# Trimble_Thunderbolt_Monitor_Shield_v1_0.net
KiCad netlist of a schematic drawn in EAGLE
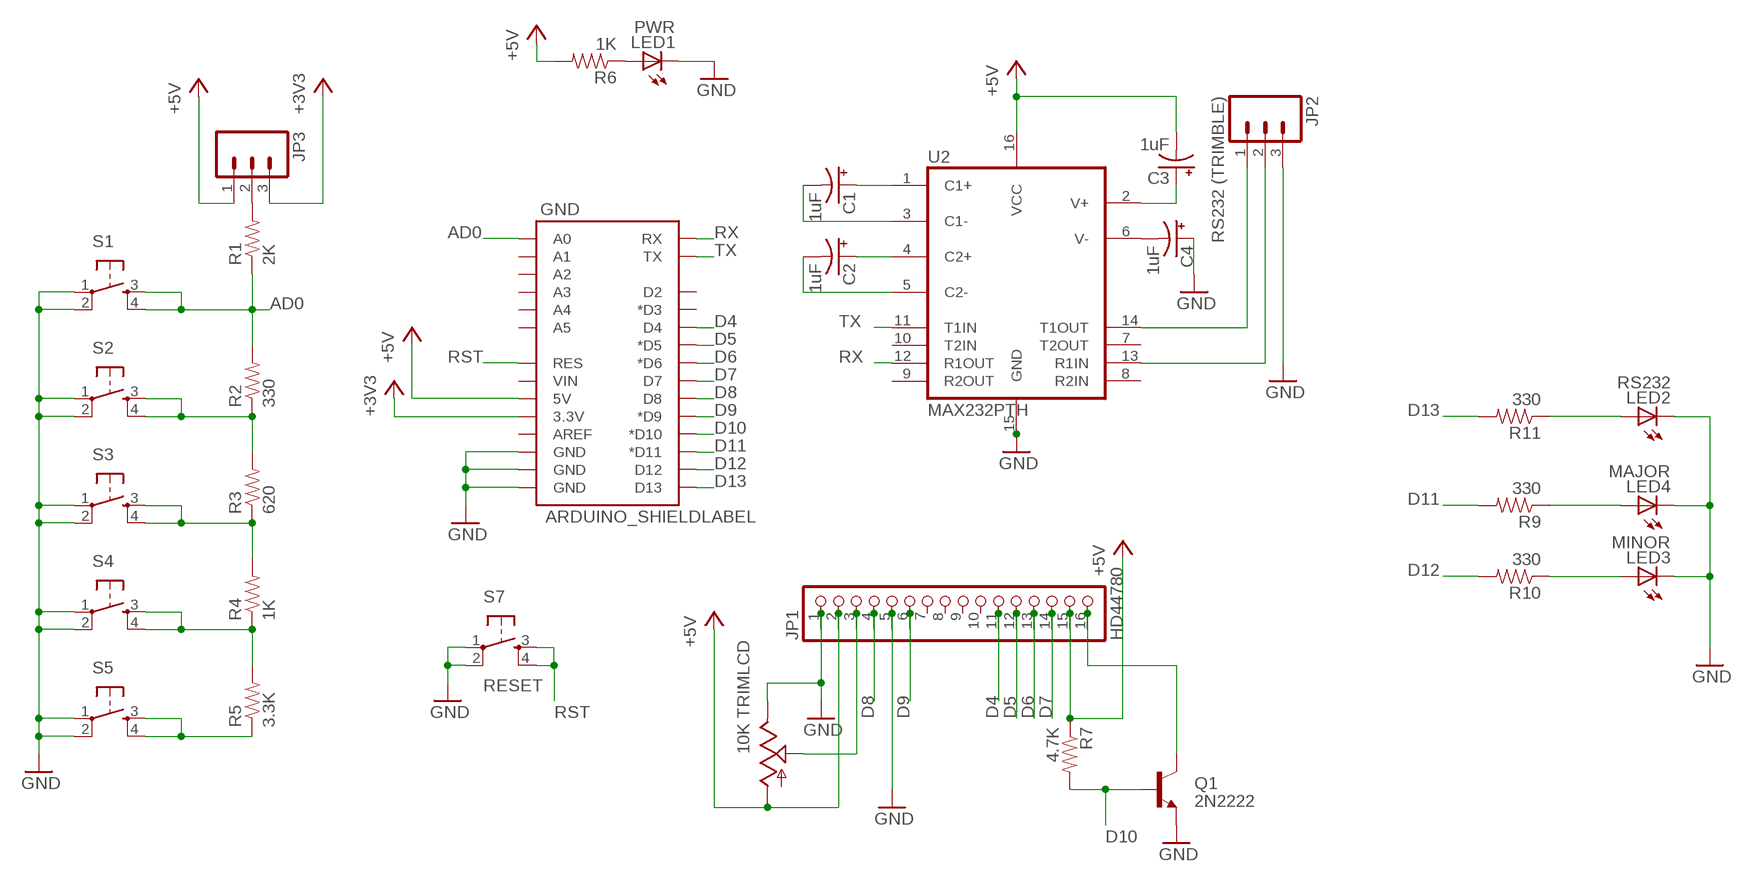
[diagram p0: schematic, sheet 1]

(export (version "E")
  (design (tool "Eeschema 10.0.6"))
  (components
    (comp (ref "C1")
      (value "1uF")
      (footprint "eagle-import:CPOL-RADIAL-10UF-25V")
      (libsource (lib "eagle-import") (part "CAP_POLPTH2"))
    )
    (comp (ref "C2")
      (value "1uF")
      (footprint "eagle-import:CPOL-RADIAL-10UF-25V")
      (libsource (lib "eagle-import") (part "CAP_POLPTH2"))
    )
    (comp (ref "C3")
      (value "1uF")
      (footprint "eagle-import:CPOL-RADIAL-10UF-25V")
      (libsource (lib "eagle-import") (part "CAP_POLPTH2"))
    )
    (comp (ref "C4")
      (value "1uF")
      (footprint "eagle-import:CPOL-RADIAL-10UF-25V")
      (libsource (lib "eagle-import") (part "CAP_POLPTH2"))
    )
    (comp (ref "GND")
      (value "ARDUINO_SHIELDLABEL")
      (footprint "eagle-import:DUEMILANOVE_SHIELD")
      (libsource (lib "eagle-import") (part "ARDUINO_SHIELDLABEL"))
    )
    (comp (ref "JP1")
      (value "HD44780")
      (footprint "eagle-import:1X16")
      (libsource (lib "eagle-import") (part "PINHD-1X16"))
    )
    (comp (ref "JP2")
      (value "RS232 (TRIMBLE)")
      (footprint "eagle-import:MOLEX-1X3")
      (libsource (lib "eagle-import") (part "M03POLAR"))
    )
    (comp (ref "JP3")
      (value "M03PTH")
      (footprint "eagle-import:1X03")
      (libsource (lib "eagle-import") (part "M03PTH"))
    )
    (comp (ref "LED1")
      (value "PWR")
      (footprint "eagle-import:LED5MM")
      (libsource (lib "eagle-import") (part "LED5MM"))
    )
    (comp (ref "LED2")
      (value "RS232")
      (footprint "eagle-import:LED5MM")
      (libsource (lib "eagle-import") (part "LED5MM"))
    )
    (comp (ref "LED3")
      (value "MINOR")
      (footprint "eagle-import:LED5MM")
      (libsource (lib "eagle-import") (part "LED5MM"))
    )
    (comp (ref "LED4")
      (value "MAJOR")
      (footprint "eagle-import:LED5MM")
      (libsource (lib "eagle-import") (part "LED5MM"))
    )
    (comp (ref "Q1")
      (value "2N2222")
      (footprint "eagle-import:TO-92-AMMO")
      (libsource (lib "eagle-import") (part "TRANSISTOR_NPNTO-92-AMMO"))
    )
    (comp (ref "R1")
      (value "2K")
      (footprint "eagle-import:AXIAL-0.3")
      (libsource (lib "eagle-import") (part "RESISTORAXIAL-0.3"))
    )
    (comp (ref "R2")
      (value "330")
      (footprint "eagle-import:AXIAL-0.3")
      (libsource (lib "eagle-import") (part "RESISTORAXIAL-0.3"))
    )
    (comp (ref "R3")
      (value "620")
      (footprint "eagle-import:AXIAL-0.3")
      (libsource (lib "eagle-import") (part "RESISTORAXIAL-0.3"))
    )
    (comp (ref "R4")
      (value "1K")
      (footprint "eagle-import:AXIAL-0.3")
      (libsource (lib "eagle-import") (part "RESISTORAXIAL-0.3"))
    )
    (comp (ref "R5")
      (value "3.3K")
      (footprint "eagle-import:AXIAL-0.3")
      (libsource (lib "eagle-import") (part "RESISTORAXIAL-0.3"))
    )
    (comp (ref "R6")
      (value "1K")
      (footprint "eagle-import:AXIAL-0.3")
      (libsource (lib "eagle-import") (part "RESISTORAXIAL-0.3"))
    )
    (comp (ref "R7")
      (value "4.7K")
      (footprint "eagle-import:AXIAL-0.3")
      (libsource (lib "eagle-import") (part "RESISTORAXIAL-0.3"))
    )
    (comp (ref "R9")
      (value "330")
      (footprint "eagle-import:AXIAL-0.3")
      (libsource (lib "eagle-import") (part "RESISTORAXIAL-0.3"))
    )
    (comp (ref "R10")
      (value "330")
      (footprint "eagle-import:AXIAL-0.3")
      (libsource (lib "eagle-import") (part "RESISTORAXIAL-0.3"))
    )
    (comp (ref "R11")
      (value "330")
      (footprint "eagle-import:AXIAL-0.3")
      (libsource (lib "eagle-import") (part "RESISTORAXIAL-0.3"))
    )
    (comp (ref "S1")
      (value "TAC_SWITCHPTH")
      (footprint "eagle-import:TACTILE-PTH")
      (libsource (lib "eagle-import") (part "TAC_SWITCHPTH"))
    )
    (comp (ref "S2")
      (value "TAC_SWITCHPTH")
      (footprint "eagle-import:TACTILE-PTH")
      (libsource (lib "eagle-import") (part "TAC_SWITCHPTH"))
    )
    (comp (ref "S3")
      (value "TAC_SWITCHPTH")
      (footprint "eagle-import:TACTILE-PTH")
      (libsource (lib "eagle-import") (part "TAC_SWITCHPTH"))
    )
    (comp (ref "S4")
      (value "TAC_SWITCHPTH")
      (footprint "eagle-import:TACTILE-PTH")
      (libsource (lib "eagle-import") (part "TAC_SWITCHPTH"))
    )
    (comp (ref "S5")
      (value "TAC_SWITCHPTH")
      (footprint "eagle-import:TACTILE-PTH")
      (libsource (lib "eagle-import") (part "TAC_SWITCHPTH"))
    )
    (comp (ref "S7")
      (value "RESET")
      (footprint "eagle-import:TACTILE-PTH")
      (libsource (lib "eagle-import") (part "TAC_SWITCHPTH"))
    )
    (comp (ref "TRIMLCD")
      (value "10K")
      (footprint "eagle-import:3362U")
      (libsource (lib "eagle-import") (part "POT100K_3362U"))
    )
    (comp (ref "U2")
      (value "MAX232PTH")
      (footprint "eagle-import:DIL16")
      (libsource (lib "eagle-import") (part "MAX232PTH"))
    )
  )
  (nets
    (net (code "1") (name "+3V3") (class "Default")
      (node (ref "GND") (pin "3.3V") (pinfunction "3.3V_3.3V") (pintype "bidirectional"))
      (node (ref "JP3") (pin "3") (pinfunction "3_3") (pintype "passive"))
    )
    (net (code "2") (name "+5V") (class "Default")
      (node (ref "C3") (pin "2") (pinfunction "-_2") (pintype "passive"))
      (node (ref "GND") (pin "5V") (pinfunction "5V_5V") (pintype "bidirectional"))
      (node (ref "JP1") (pin "15") (pinfunction "15_15") (pintype "passive"))
      (node (ref "JP1") (pin "2") (pinfunction "2_2") (pintype "passive"))
      (node (ref "JP3") (pin "1") (pinfunction "1_1") (pintype "passive"))
      (node (ref "R6") (pin "P$2") (pinfunction "2_P$2") (pintype "passive"))
      (node (ref "R7") (pin "P$1") (pinfunction "1_P$1") (pintype "passive"))
      (node (ref "TRIMLCD") (pin "P$3") (pinfunction "A_P$3") (pintype "passive"))
      (node (ref "U2") (pin "16") (pinfunction "VCC_16") (pintype "bidirectional"))
    )
    (net (code "3") (name "/AD0") (class "Default")
      (node (ref "GND") (pin "A0") (pinfunction "A0_A0") (pintype "bidirectional"))
      (node (ref "R1") (pin "P$1") (pinfunction "1_P$1") (pintype "passive"))
      (node (ref "R2") (pin "P$2") (pinfunction "2_P$2") (pintype "passive"))
      (node (ref "S1") (pin "3") (pinfunction "3_3") (pintype "passive"))
      (node (ref "S1") (pin "4") (pinfunction "4_4") (pintype "passive"))
    )
    (net (code "4") (name "/D4") (class "Default")
      (node (ref "GND") (pin "D4") (pinfunction "D4_D4") (pintype "bidirectional"))
      (node (ref "JP1") (pin "11") (pinfunction "11_11") (pintype "passive"))
    )
    (net (code "5") (name "/D5") (class "Default")
      (node (ref "GND") (pin "D5") (pinfunction "*D5_D5") (pintype "bidirectional"))
      (node (ref "JP1") (pin "12") (pinfunction "12_12") (pintype "passive"))
    )
    (net (code "6") (name "/D6") (class "Default")
      (node (ref "GND") (pin "D6") (pinfunction "*D6_D6") (pintype "bidirectional"))
      (node (ref "JP1") (pin "13") (pinfunction "13_13") (pintype "passive"))
    )
    (net (code "7") (name "/D7") (class "Default")
      (node (ref "GND") (pin "D7") (pinfunction "D7_D7") (pintype "bidirectional"))
      (node (ref "JP1") (pin "14") (pinfunction "14_14") (pintype "passive"))
    )
    (net (code "8") (name "/D8") (class "Default")
      (node (ref "GND") (pin "D8") (pinfunction "D8_D8") (pintype "bidirectional"))
      (node (ref "JP1") (pin "4") (pinfunction "4_4") (pintype "passive"))
    )
    (net (code "9") (name "/D9") (class "Default")
      (node (ref "GND") (pin "D9") (pinfunction "*D9_D9") (pintype "bidirectional"))
      (node (ref "JP1") (pin "6") (pinfunction "6_6") (pintype "passive"))
    )
    (net (code "10") (name "/D10") (class "Default")
      (node (ref "GND") (pin "D10") (pinfunction "*D10_D10") (pintype "bidirectional"))
      (node (ref "Q1") (pin "2") (pinfunction "B_2") (pintype "passive"))
      (node (ref "R7") (pin "P$2") (pinfunction "2_P$2") (pintype "passive"))
    )
    (net (code "11") (name "/D11") (class "Default")
      (node (ref "GND") (pin "D11") (pinfunction "*D11_D11") (pintype "bidirectional"))
      (node (ref "R9") (pin "P$2") (pinfunction "2_P$2") (pintype "passive"))
    )
    (net (code "12") (name "/D12") (class "Default")
      (node (ref "GND") (pin "D12") (pinfunction "D12_D12") (pintype "bidirectional"))
      (node (ref "R10") (pin "P$2") (pinfunction "2_P$2") (pintype "passive"))
    )
    (net (code "13") (name "/D13") (class "Default")
      (node (ref "GND") (pin "D13") (pinfunction "D13_D13") (pintype "bidirectional"))
      (node (ref "R11") (pin "P$2") (pinfunction "2_P$2") (pintype "passive"))
    )
    (net (code "14") (name "/RST") (class "Default")
      (node (ref "GND") (pin "RES") (pinfunction "RES_RES") (pintype "bidirectional"))
      (node (ref "S7") (pin "3") (pinfunction "3_3") (pintype "passive"))
      (node (ref "S7") (pin "4") (pinfunction "4_4") (pintype "passive"))
    )
    (net (code "15") (name "/RX") (class "Default")
      (node (ref "GND") (pin "RX") (pinfunction "RX_RX") (pintype "bidirectional"))
      (node (ref "U2") (pin "12") (pinfunction "R1OUT_12") (pintype "output"))
    )
    (net (code "16") (name "/TX") (class "Default")
      (node (ref "GND") (pin "TX") (pinfunction "TX_TX") (pintype "bidirectional"))
      (node (ref "U2") (pin "11") (pinfunction "T1IN_11") (pintype "input"))
    )
    (net (code "17") (name "GND") (class "Default")
      (node (ref "C4") (pin "1") (pinfunction "+_1") (pintype "passive"))
      (node (ref "GND") (pin "GND@0") (pinfunction "GND_GND@0") (pintype "bidirectional"))
      (node (ref "GND") (pin "GND@1") (pinfunction "GND_GND@1") (pintype "bidirectional"))
      (node (ref "GND") (pin "GND@2") (pinfunction "GND_GND@2") (pintype "bidirectional"))
      (node (ref "JP1") (pin "1") (pinfunction "1_1") (pintype "passive"))
      (node (ref "JP1") (pin "5") (pinfunction "5_5") (pintype "passive"))
      (node (ref "JP2") (pin "3") (pinfunction "3_3") (pintype "passive"))
      (node (ref "LED1") (pin "K") (pinfunction "C_K") (pintype "passive"))
      (node (ref "LED2") (pin "K") (pinfunction "C_K") (pintype "passive"))
      (node (ref "LED3") (pin "K") (pinfunction "C_K") (pintype "passive"))
      (node (ref "LED4") (pin "K") (pinfunction "C_K") (pintype "passive"))
      (node (ref "Q1") (pin "1") (pinfunction "E_1") (pintype "passive"))
      (node (ref "S1") (pin "1") (pinfunction "1_1") (pintype "passive"))
      (node (ref "S1") (pin "2") (pinfunction "2_2") (pintype "passive"))
      (node (ref "S2") (pin "1") (pinfunction "1_1") (pintype "passive"))
      (node (ref "S2") (pin "2") (pinfunction "2_2") (pintype "passive"))
      (node (ref "S3") (pin "1") (pinfunction "1_1") (pintype "passive"))
      (node (ref "S3") (pin "2") (pinfunction "2_2") (pintype "passive"))
      (node (ref "S4") (pin "1") (pinfunction "1_1") (pintype "passive"))
      (node (ref "S4") (pin "2") (pinfunction "2_2") (pintype "passive"))
      (node (ref "S5") (pin "1") (pinfunction "1_1") (pintype "passive"))
      (node (ref "S5") (pin "2") (pinfunction "2_2") (pintype "passive"))
      (node (ref "S7") (pin "1") (pinfunction "1_1") (pintype "passive"))
      (node (ref "S7") (pin "2") (pinfunction "2_2") (pintype "passive"))
      (node (ref "TRIMLCD") (pin "P$1") (pinfunction "E_P$1") (pintype "passive"))
      (node (ref "U2") (pin "15") (pinfunction "GND_15") (pintype "bidirectional"))
    )
    (net (code "18") (name "Net-(C1-+)") (class "Default")
      (node (ref "C1") (pin "1") (pinfunction "+_1") (pintype "passive"))
      (node (ref "U2") (pin "1") (pinfunction "C1+_1") (pintype "bidirectional"))
    )
    (net (code "19") (name "Net-(C1--)") (class "Default")
      (node (ref "C1") (pin "2") (pinfunction "-_2") (pintype "passive"))
      (node (ref "U2") (pin "3") (pinfunction "C1-_3") (pintype "bidirectional"))
    )
    (net (code "20") (name "Net-(C2-+)") (class "Default")
      (node (ref "C2") (pin "1") (pinfunction "+_1") (pintype "passive"))
      (node (ref "U2") (pin "4") (pinfunction "C2+_4") (pintype "bidirectional"))
    )
    (net (code "21") (name "Net-(C2--)") (class "Default")
      (node (ref "C2") (pin "2") (pinfunction "-_2") (pintype "passive"))
      (node (ref "U2") (pin "5") (pinfunction "C2-_5") (pintype "bidirectional"))
    )
    (net (code "22") (name "Net-(C3-+)") (class "Default")
      (node (ref "C3") (pin "1") (pinfunction "+_1") (pintype "passive"))
      (node (ref "U2") (pin "2") (pinfunction "V+_2") (pintype "bidirectional"))
    )
    (net (code "23") (name "Net-(C4--)") (class "Default")
      (node (ref "C4") (pin "2") (pinfunction "-_2") (pintype "passive"))
      (node (ref "U2") (pin "6") (pinfunction "V-_6") (pintype "bidirectional"))
    )
    (net (code "24") (name "Net-(Q1-C)") (class "Default")
      (node (ref "JP1") (pin "16") (pinfunction "16_16") (pintype "passive"))
      (node (ref "Q1") (pin "3") (pinfunction "C_3") (pintype "passive"))
    )
    (net (code "25") (name "Net-(R1-2)") (class "Default")
      (node (ref "JP3") (pin "2") (pinfunction "2_2") (pintype "passive"))
      (node (ref "R1") (pin "P$2") (pinfunction "2_P$2") (pintype "passive"))
    )
    (net (code "26") (name "Net-(R2-1)") (class "Default")
      (node (ref "R2") (pin "P$1") (pinfunction "1_P$1") (pintype "passive"))
      (node (ref "R3") (pin "P$2") (pinfunction "2_P$2") (pintype "passive"))
      (node (ref "S2") (pin "3") (pinfunction "3_3") (pintype "passive"))
      (node (ref "S2") (pin "4") (pinfunction "4_4") (pintype "passive"))
    )
    (net (code "27") (name "Net-(R3-1)") (class "Default")
      (node (ref "R3") (pin "P$1") (pinfunction "1_P$1") (pintype "passive"))
      (node (ref "R4") (pin "P$2") (pinfunction "2_P$2") (pintype "passive"))
      (node (ref "S3") (pin "3") (pinfunction "3_3") (pintype "passive"))
      (node (ref "S3") (pin "4") (pinfunction "4_4") (pintype "passive"))
    )
    (net (code "28") (name "Net-(R4-1)") (class "Default")
      (node (ref "R4") (pin "P$1") (pinfunction "1_P$1") (pintype "passive"))
      (node (ref "R5") (pin "P$2") (pinfunction "2_P$2") (pintype "passive"))
      (node (ref "S4") (pin "3") (pinfunction "3_3") (pintype "passive"))
      (node (ref "S4") (pin "4") (pinfunction "4_4") (pintype "passive"))
    )
    (net (code "29") (name "Net-(R5-1)") (class "Default")
      (node (ref "R5") (pin "P$1") (pinfunction "1_P$1") (pintype "passive"))
      (node (ref "S5") (pin "3") (pinfunction "3_3") (pintype "passive"))
      (node (ref "S5") (pin "4") (pinfunction "4_4") (pintype "passive"))
    )
    (net (code "30") (name "Net-(R6-1)") (class "Default")
      (node (ref "LED1") (pin "A") (pinfunction "A_A") (pintype "passive"))
      (node (ref "R6") (pin "P$1") (pinfunction "1_P$1") (pintype "passive"))
    )
    (net (code "31") (name "Net-(R9-1)") (class "Default")
      (node (ref "LED4") (pin "A") (pinfunction "A_A") (pintype "passive"))
      (node (ref "R9") (pin "P$1") (pinfunction "1_P$1") (pintype "passive"))
    )
    (net (code "32") (name "Net-(R10-1)") (class "Default")
      (node (ref "LED3") (pin "A") (pinfunction "A_A") (pintype "passive"))
      (node (ref "R10") (pin "P$1") (pinfunction "1_P$1") (pintype "passive"))
    )
    (net (code "33") (name "Net-(R11-1)") (class "Default")
      (node (ref "LED2") (pin "A") (pinfunction "A_A") (pintype "passive"))
      (node (ref "R11") (pin "P$1") (pinfunction "1_P$1") (pintype "passive"))
    )
    (net (code "34") (name "Net-(TRIMLCD-S)") (class "Default")
      (node (ref "JP1") (pin "3") (pinfunction "3_3") (pintype "passive"))
      (node (ref "TRIMLCD") (pin "P$2") (pinfunction "S_P$2") (pintype "passive"))
    )
    (net (code "35") (name "Net-(U2-R1IN)") (class "Default")
      (node (ref "JP2") (pin "2") (pinfunction "2_2") (pintype "passive"))
      (node (ref "U2") (pin "13") (pinfunction "R1IN_13") (pintype "input"))
    )
    (net (code "36") (name "Net-(U2-T1OUT)") (class "Default")
      (node (ref "JP2") (pin "1") (pinfunction "1_1") (pintype "passive"))
      (node (ref "U2") (pin "14") (pinfunction "T1OUT_14") (pintype "output"))
    )
    (net (code "37") (name "unconnected-(GND-*D3-PadD3)") (class "Default")
      (node (ref "GND") (pin "D3") (pinfunction "*D3_D3") (pintype "bidirectional"))
    )
    (net (code "38") (name "unconnected-(GND-PadA1)") (class "Default")
      (node (ref "GND") (pin "A1") (pinfunction "A1_A1") (pintype "bidirectional"))
    )
    (net (code "39") (name "unconnected-(GND-PadA2)") (class "Default")
      (node (ref "GND") (pin "A2") (pinfunction "A2_A2") (pintype "bidirectional"))
    )
    (net (code "40") (name "unconnected-(GND-PadA3)") (class "Default")
      (node (ref "GND") (pin "A3") (pinfunction "A3_A3") (pintype "bidirectional"))
    )
    (net (code "41") (name "unconnected-(GND-PadA4)") (class "Default")
      (node (ref "GND") (pin "A4") (pinfunction "A4_A4") (pintype "bidirectional"))
    )
    (net (code "42") (name "unconnected-(GND-PadA5)") (class "Default")
      (node (ref "GND") (pin "A5") (pinfunction "A5_A5") (pintype "bidirectional"))
    )
    (net (code "43") (name "unconnected-(GND-PadAREF)") (class "Default")
      (node (ref "GND") (pin "AREF") (pinfunction "AREF_AREF") (pintype "bidirectional"))
    )
    (net (code "44") (name "unconnected-(GND-PadD2)") (class "Default")
      (node (ref "GND") (pin "D2") (pinfunction "D2_D2") (pintype "bidirectional"))
    )
    (net (code "45") (name "unconnected-(GND-PadVIN)") (class "Default")
      (node (ref "GND") (pin "VIN") (pinfunction "VIN_VIN") (pintype "bidirectional"))
    )
    (net (code "46") (name "unconnected-(JP1-Pad7)") (class "Default")
      (node (ref "JP1") (pin "7") (pinfunction "7_7") (pintype "passive"))
    )
    (net (code "47") (name "unconnected-(JP1-Pad8)") (class "Default")
      (node (ref "JP1") (pin "8") (pinfunction "8_8") (pintype "passive"))
    )
    (net (code "48") (name "unconnected-(JP1-Pad9)") (class "Default")
      (node (ref "JP1") (pin "9") (pinfunction "9_9") (pintype "passive"))
    )
    (net (code "49") (name "unconnected-(JP1-Pad10)") (class "Default")
      (node (ref "JP1") (pin "10") (pinfunction "10_10") (pintype "passive"))
    )
    (net (code "50") (name "unconnected-(U2-R2IN-Pad8)") (class "Default")
      (node (ref "U2") (pin "8") (pinfunction "R2IN_8") (pintype "input"))
    )
    (net (code "51") (name "unconnected-(U2-R2OUT-Pad9)") (class "Default")
      (node (ref "U2") (pin "9") (pinfunction "R2OUT_9") (pintype "output"))
    )
    (net (code "52") (name "unconnected-(U2-T2IN-Pad10)") (class "Default")
      (node (ref "U2") (pin "10") (pinfunction "T2IN_10") (pintype "input"))
    )
    (net (code "53") (name "unconnected-(U2-T2OUT-Pad7)") (class "Default")
      (node (ref "U2") (pin "7") (pinfunction "T2OUT_7") (pintype "output"))
    )
  )
)
